# pcb_business_card.net
KiCad netlist of a schematic drawn in EAGLE
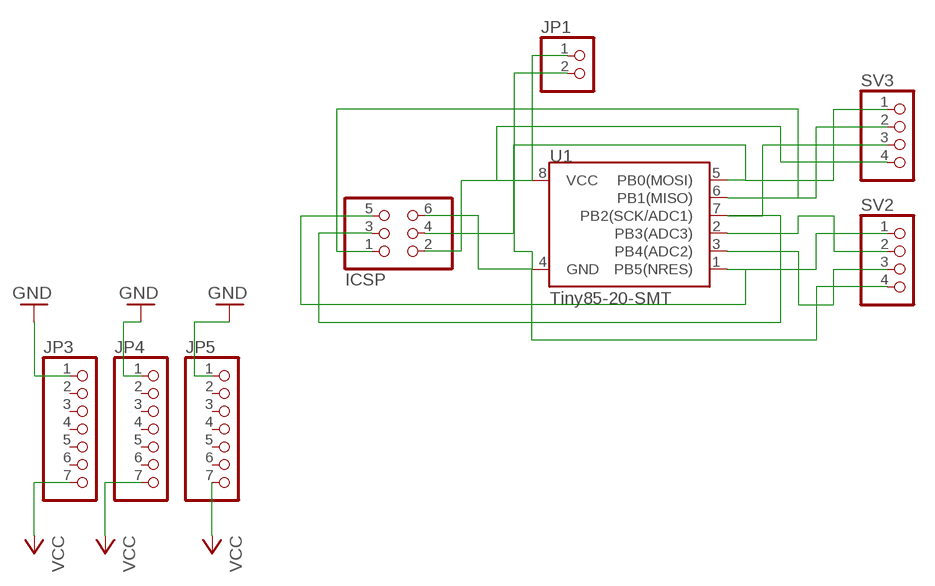
[diagram p0: schematic, sheet 1]

(export (version "E")
  (design (tool "Eeschema 10.0.6"))
  (components
    (comp (ref "ICSP")
      (value "PINHD-2X3")
      (footprint "eagle-import:2X03")
      (libsource (lib "eagle-import") (part "PINHD-2X3"))
    )
    (comp (ref "JP1")
      (value "PINHD-1X2")
      (footprint "eagle-import:1X02")
      (libsource (lib "eagle-import") (part "PINHD-1X2"))
    )
    (comp (ref "JP3")
      (value "PINHD-1X7")
      (footprint "eagle-import:1X07")
      (libsource (lib "eagle-import") (part "PINHD-1X7"))
    )
    (comp (ref "JP4")
      (value "PINHD-1X7")
      (footprint "eagle-import:1X07")
      (libsource (lib "eagle-import") (part "PINHD-1X7"))
    )
    (comp (ref "JP5")
      (value "PINHD-1X7")
      (footprint "eagle-import:1X07")
      (libsource (lib "eagle-import") (part "PINHD-1X7"))
    )
    (comp (ref "SV2")
      (value "PINHD-1X4")
      (footprint "eagle-import:1X04")
      (libsource (lib "eagle-import") (part "PINHD-1X4"))
    )
    (comp (ref "SV3")
      (value "PINHD-1X4")
      (footprint "eagle-import:1X04")
      (libsource (lib "eagle-import") (part "PINHD-1X4"))
    )
    (comp (ref "U1")
      (value "Tiny85-20-SMT")
      (footprint "eagle-import:SO08-EIAJ")
      (libsource (lib "eagle-import") (part "ATTINY45TINY85-20-SMT"))
    )
  )
  (nets
    (net (code "1") (name "GND") (class "Default")
      (node (ref "ICSP") (pin "6") (pinfunction "6_6") (pintype "passive"))
      (node (ref "JP1") (pin "2") (pinfunction "2_2") (pintype "passive"))
      (node (ref "JP3") (pin "1") (pinfunction "1_1") (pintype "passive"))
      (node (ref "JP4") (pin "1") (pinfunction "1_1") (pintype "passive"))
      (node (ref "JP5") (pin "1") (pinfunction "1_1") (pintype "passive"))
      (node (ref "SV2") (pin "4") (pinfunction "4_4") (pintype "passive"))
      (node (ref "U1") (pin "4") (pinfunction "GND_4") (pintype "bidirectional"))
    )
    (net (code "2") (name "Net-(U1-PB0(MOSI))") (class "Default")
      (node (ref "ICSP") (pin "4") (pinfunction "4_4") (pintype "passive"))
      (node (ref "SV3") (pin "1") (pinfunction "1_1") (pintype "passive"))
      (node (ref "U1") (pin "5") (pinfunction "PB0(MOSI)_5") (pintype "bidirectional"))
    )
    (net (code "3") (name "Net-(U1-PB1(MISO))") (class "Default")
      (node (ref "ICSP") (pin "1") (pinfunction "1_1") (pintype "passive"))
      (node (ref "SV3") (pin "2") (pinfunction "2_2") (pintype "passive"))
      (node (ref "U1") (pin "6") (pinfunction "PB1(MISO)_6") (pintype "bidirectional"))
    )
    (net (code "4") (name "Net-(U1-PB2(SCK{slash}ADC1))") (class "Default")
      (node (ref "ICSP") (pin "3") (pinfunction "3_3") (pintype "passive"))
      (node (ref "SV3") (pin "3") (pinfunction "3_3") (pintype "passive"))
      (node (ref "U1") (pin "7") (pinfunction "PB2(SCK/ADC1)_7") (pintype "bidirectional"))
    )
    (net (code "5") (name "Net-(U1-PB3(ADC3))") (class "Default")
      (node (ref "SV2") (pin "2") (pinfunction "2_2") (pintype "passive"))
      (node (ref "U1") (pin "2") (pinfunction "PB3(ADC3)_2") (pintype "bidirectional"))
    )
    (net (code "6") (name "Net-(U1-PB4(ADC2))") (class "Default")
      (node (ref "SV2") (pin "3") (pinfunction "3_3") (pintype "passive"))
      (node (ref "U1") (pin "3") (pinfunction "PB4(ADC2)_3") (pintype "bidirectional"))
    )
    (net (code "7") (name "Net-(U1-PB5(NRES))") (class "Default")
      (node (ref "ICSP") (pin "5") (pinfunction "5_5") (pintype "passive"))
      (node (ref "SV2") (pin "1") (pinfunction "1_1") (pintype "passive"))
      (node (ref "U1") (pin "1") (pinfunction "PB5(NRES)_1") (pintype "bidirectional"))
    )
    (net (code "8") (name "VCC") (class "Default")
      (node (ref "ICSP") (pin "2") (pinfunction "2_2") (pintype "passive"))
      (node (ref "JP1") (pin "1") (pinfunction "1_1") (pintype "passive"))
      (node (ref "JP3") (pin "7") (pinfunction "7_7") (pintype "passive"))
      (node (ref "JP4") (pin "7") (pinfunction "7_7") (pintype "passive"))
      (node (ref "JP5") (pin "7") (pinfunction "7_7") (pintype "passive"))
      (node (ref "SV3") (pin "4") (pinfunction "4_4") (pintype "passive"))
      (node (ref "U1") (pin "8") (pinfunction "VCC_8") (pintype "bidirectional"))
    )
    (net (code "9") (name "unconnected-(JP3-Pad2)") (class "Default")
      (node (ref "JP3") (pin "2") (pinfunction "2_2") (pintype "passive"))
    )
    (net (code "10") (name "unconnected-(JP3-Pad3)") (class "Default")
      (node (ref "JP3") (pin "3") (pinfunction "3_3") (pintype "passive"))
    )
    (net (code "11") (name "unconnected-(JP3-Pad4)") (class "Default")
      (node (ref "JP3") (pin "4") (pinfunction "4_4") (pintype "passive"))
    )
    (net (code "12") (name "unconnected-(JP3-Pad5)") (class "Default")
      (node (ref "JP3") (pin "5") (pinfunction "5_5") (pintype "passive"))
    )
    (net (code "13") (name "unconnected-(JP3-Pad6)") (class "Default")
      (node (ref "JP3") (pin "6") (pinfunction "6_6") (pintype "passive"))
    )
    (net (code "14") (name "unconnected-(JP4-Pad2)") (class "Default")
      (node (ref "JP4") (pin "2") (pinfunction "2_2") (pintype "passive"))
    )
    (net (code "15") (name "unconnected-(JP4-Pad3)") (class "Default")
      (node (ref "JP4") (pin "3") (pinfunction "3_3") (pintype "passive"))
    )
    (net (code "16") (name "unconnected-(JP4-Pad4)") (class "Default")
      (node (ref "JP4") (pin "4") (pinfunction "4_4") (pintype "passive"))
    )
    (net (code "17") (name "unconnected-(JP4-Pad5)") (class "Default")
      (node (ref "JP4") (pin "5") (pinfunction "5_5") (pintype "passive"))
    )
    (net (code "18") (name "unconnected-(JP4-Pad6)") (class "Default")
      (node (ref "JP4") (pin "6") (pinfunction "6_6") (pintype "passive"))
    )
    (net (code "19") (name "unconnected-(JP5-Pad2)") (class "Default")
      (node (ref "JP5") (pin "2") (pinfunction "2_2") (pintype "passive"))
    )
    (net (code "20") (name "unconnected-(JP5-Pad3)") (class "Default")
      (node (ref "JP5") (pin "3") (pinfunction "3_3") (pintype "passive"))
    )
    (net (code "21") (name "unconnected-(JP5-Pad4)") (class "Default")
      (node (ref "JP5") (pin "4") (pinfunction "4_4") (pintype "passive"))
    )
    (net (code "22") (name "unconnected-(JP5-Pad5)") (class "Default")
      (node (ref "JP5") (pin "5") (pinfunction "5_5") (pintype "passive"))
    )
    (net (code "23") (name "unconnected-(JP5-Pad6)") (class "Default")
      (node (ref "JP5") (pin "6") (pinfunction "6_6") (pintype "passive"))
    )
  )
)
